# SheetAmpli.net
KiCad netlist of a schematic drawn in Altium Designer
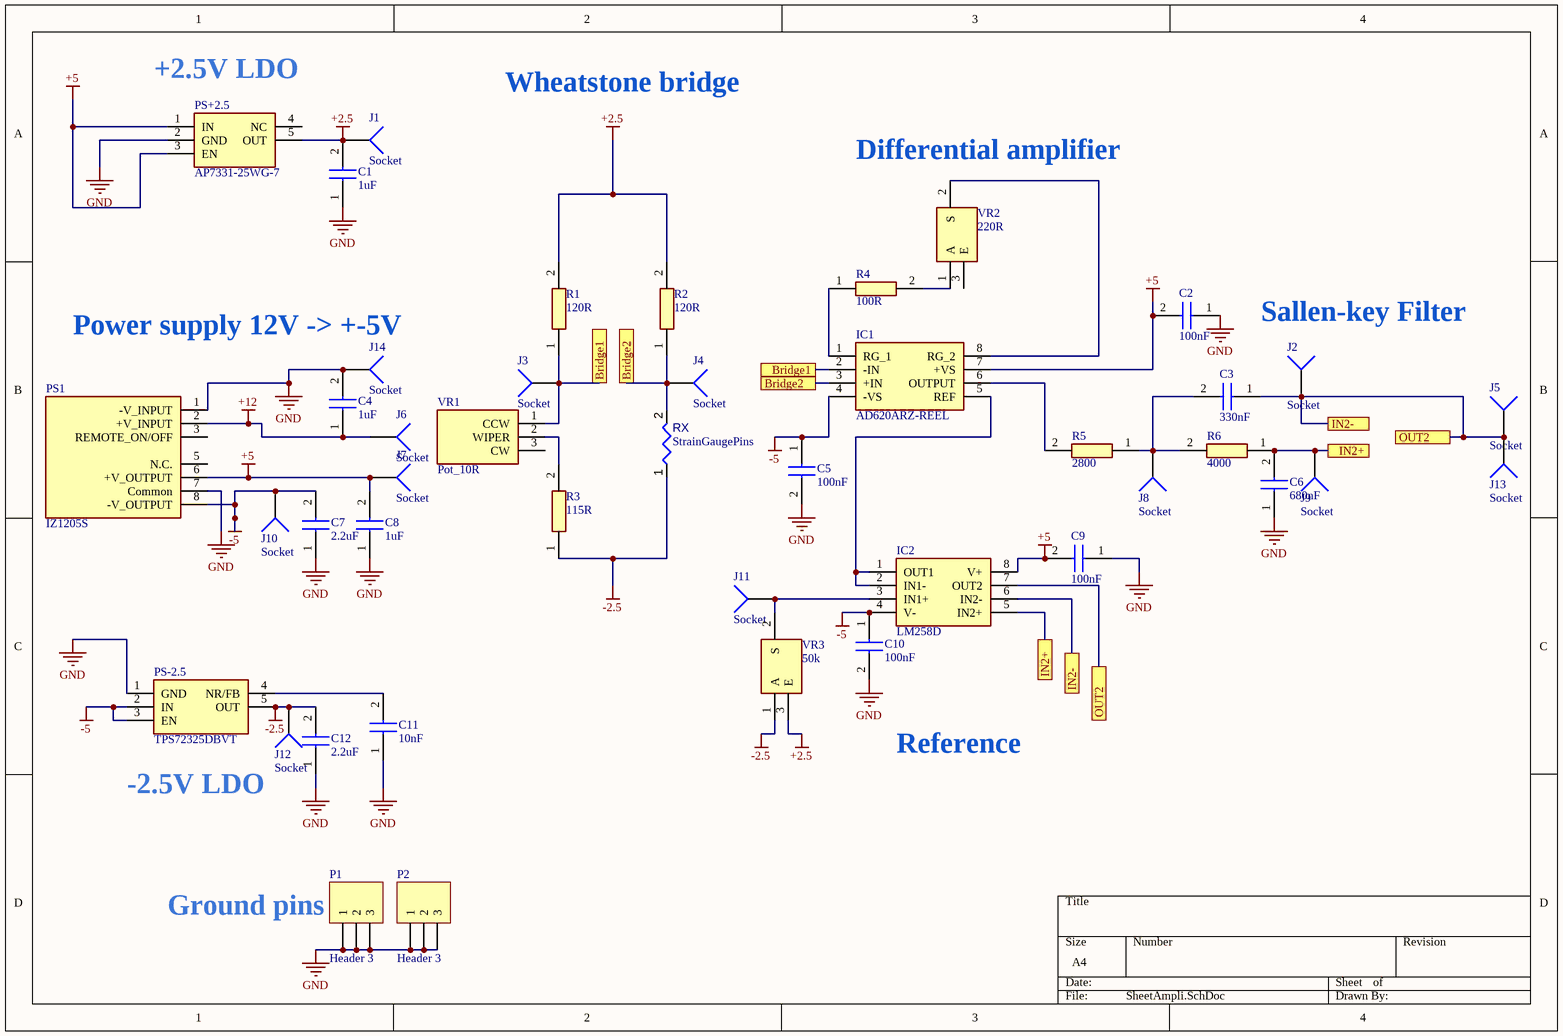
[diagram p0: SheetAmpli.SchDoc]

(export (version "E")
  (design (tool "Eeschema 10.0.6"))
  (components
    (comp (ref "C1")
      (value "1uF")
      (footprint "SamacSys:CAPC2012X94N")
      (description "Capacitor")
      (fields
        (field (name "MANUFACTURER_PART_NUMBER") "08055A130JAT2A")
        (field (name "MOUSER PART NUMBER") "581-08055A130JAT2A")
      )
      (libsource (lib "*") (part "08055A130JAT2A"))
    )
    (comp (ref "C2")
      (value "100nF")
      (footprint "SamacSys:CAPC2012X94N")
      (description "Capacitor")
      (fields
        (field (name "MANUFACTURER_PART_NUMBER") "08055A130JAT2A")
        (field (name "MOUSER PART NUMBER") "581-08055A130JAT2A")
      )
      (libsource (lib "*") (part "08055A130JAT2A"))
    )
    (comp (ref "C3")
      (value "330nF")
      (footprint "SamacSys:CAPC2012X94N")
      (description "Capacitor")
      (fields
        (field (name "MANUFACTURER_PART_NUMBER") "08055A130JAT2A")
        (field (name "MOUSER PART NUMBER") "581-08055A130JAT2A")
      )
      (libsource (lib "*") (part "08055A130JAT2A"))
    )
    (comp (ref "C4")
      (value "1uF")
      (footprint "SamacSys:CAPC2012X94N")
      (description "Capacitor")
      (fields
        (field (name "MANUFACTURER_PART_NUMBER") "08055A130JAT2A")
        (field (name "MOUSER PART NUMBER") "581-08055A130JAT2A")
      )
      (libsource (lib "*") (part "08055A130JAT2A"))
    )
    (comp (ref "C5")
      (value "100nF")
      (footprint "SamacSys:CAPC2012X94N")
      (description "Capacitor")
      (fields
        (field (name "MANUFACTURER_PART_NUMBER") "08055A130JAT2A")
        (field (name "MOUSER PART NUMBER") "581-08055A130JAT2A")
      )
      (libsource (lib "*") (part "08055A130JAT2A"))
    )
    (comp (ref "C6")
      (value "680nF")
      (footprint "SamacSys:CAPC2012X94N")
      (description "Capacitor")
      (fields
        (field (name "MANUFACTURER_PART_NUMBER") "08055A130JAT2A")
        (field (name "MOUSER PART NUMBER") "581-08055A130JAT2A")
      )
      (libsource (lib "*") (part "08055A130JAT2A"))
    )
    (comp (ref "C7")
      (value "2.2uF")
      (footprint "SamacSys:CAPC2012X94N")
      (description "Capacitor")
      (fields
        (field (name "MANUFACTURER_PART_NUMBER") "08055A130JAT2A")
        (field (name "MOUSER PART NUMBER") "581-08055A130JAT2A")
      )
      (libsource (lib "*") (part "08055A130JAT2A"))
    )
    (comp (ref "C8")
      (value "1uF")
      (footprint "SamacSys:CAPC2012X94N")
      (description "Capacitor")
      (fields
        (field (name "MANUFACTURER_PART_NUMBER") "08055A130JAT2A")
        (field (name "MOUSER PART NUMBER") "581-08055A130JAT2A")
      )
      (libsource (lib "*") (part "08055A130JAT2A"))
    )
    (comp (ref "C9")
      (value "100nF")
      (footprint "SamacSys:CAPC2012X94N")
      (description "Capacitor")
      (fields
        (field (name "MANUFACTURER_PART_NUMBER") "08055A130JAT2A")
        (field (name "MOUSER PART NUMBER") "581-08055A130JAT2A")
      )
      (libsource (lib "*") (part "08055A130JAT2A"))
    )
    (comp (ref "C10")
      (value "100nF")
      (footprint "SamacSys:CAPC2012X94N")
      (description "Capacitor")
      (fields
        (field (name "MANUFACTURER_PART_NUMBER") "08055A130JAT2A")
        (field (name "MOUSER PART NUMBER") "581-08055A130JAT2A")
      )
      (libsource (lib "*") (part "08055A130JAT2A"))
    )
    (comp (ref "C11")
      (value "10nF")
      (footprint "SamacSys:CAPC2012X94N")
      (description "Capacitor")
      (fields
        (field (name "MANUFACTURER_PART_NUMBER") "08055A130JAT2A")
        (field (name "MOUSER PART NUMBER") "581-08055A130JAT2A")
      )
      (libsource (lib "*") (part "08055A130JAT2A"))
    )
    (comp (ref "C12")
      (value "2.2uF")
      (footprint "SamacSys:CAPC2012X94N")
      (description "Capacitor")
      (fields
        (field (name "MANUFACTURER_PART_NUMBER") "08055A130JAT2A")
        (field (name "MOUSER PART NUMBER") "581-08055A130JAT2A")
      )
      (libsource (lib "*") (part "08055A130JAT2A"))
    )
    (comp (ref "IC1")
      (value "AD620ARZ-REEL")
      (footprint "SamacSys:SOIC127P600X175-8N")
      (description "Integrated Circuit")
      (fields (field (name "MOUSER PART NUMBER") "584-AD620ARZ-R"))
      (libsource (lib "*") (part "AD620ARZ-REEL"))
    )
    (comp (ref "IC2")
      (value "LM258D")
      (footprint "SamacSys:SOIC127P600X175-8N")
      (description "Integrated Circuit")
      (fields (field (name "MOUSER PART NUMBER") "595-LM258D"))
      (libsource (lib "*") (part "LM258D"))
    )
    (comp (ref "J1")
      (value "Socket")
      (footprint "PIN1")
      (fields (field (name "PUBLISHER") "Altium Limited"))
      (libsource (lib "Miscellaneous Connectors") (part "Socket"))
    )
    (comp (ref "J2")
      (value "Socket")
      (footprint "PIN1")
      (fields (field (name "PUBLISHER") "Altium Limited"))
      (libsource (lib "Miscellaneous Connectors") (part "Socket"))
    )
    (comp (ref "J3")
      (value "Socket")
      (footprint "PIN1")
      (fields (field (name "PUBLISHER") "Altium Limited"))
      (libsource (lib "Miscellaneous Connectors") (part "Socket"))
    )
    (comp (ref "J4")
      (value "Socket")
      (footprint "PIN1")
      (fields (field (name "PUBLISHER") "Altium Limited"))
      (libsource (lib "Miscellaneous Connectors") (part "Socket"))
    )
    (comp (ref "J5")
      (value "Socket")
      (footprint "PIN1")
      (fields (field (name "PUBLISHER") "Altium Limited"))
      (libsource (lib "Miscellaneous Connectors") (part "Socket"))
    )
    (comp (ref "J6")
      (value "Socket")
      (footprint "PIN1")
      (fields (field (name "PUBLISHER") "Altium Limited"))
      (libsource (lib "Miscellaneous Connectors") (part "Socket"))
    )
    (comp (ref "J7")
      (value "Socket")
      (footprint "PIN1")
      (fields (field (name "PUBLISHER") "Altium Limited"))
      (libsource (lib "Miscellaneous Connectors") (part "Socket"))
    )
    (comp (ref "J8")
      (value "Socket")
      (footprint "PIN1")
      (fields (field (name "PUBLISHER") "Altium Limited"))
      (libsource (lib "Miscellaneous Connectors") (part "Socket"))
    )
    (comp (ref "J9")
      (value "Socket")
      (footprint "PIN1")
      (fields (field (name "PUBLISHER") "Altium Limited"))
      (libsource (lib "Miscellaneous Connectors") (part "Socket"))
    )
    (comp (ref "J10")
      (value "Socket")
      (footprint "PIN1")
      (fields (field (name "PUBLISHER") "Altium Limited"))
      (libsource (lib "Miscellaneous Connectors") (part "Socket"))
    )
    (comp (ref "J11")
      (value "Socket")
      (footprint "PIN1")
      (fields (field (name "PUBLISHER") "Altium Limited"))
      (libsource (lib "Miscellaneous Connectors") (part "Socket"))
    )
    (comp (ref "J12")
      (value "Socket")
      (footprint "PIN1")
      (fields (field (name "PUBLISHER") "Altium Limited"))
      (libsource (lib "Miscellaneous Connectors") (part "Socket"))
    )
    (comp (ref "J13")
      (value "Socket")
      (footprint "PIN1")
      (fields (field (name "PUBLISHER") "Altium Limited"))
      (libsource (lib "Miscellaneous Connectors") (part "Socket"))
    )
    (comp (ref "J14")
      (value "Socket")
      (footprint "PIN1")
      (fields (field (name "PUBLISHER") "Altium Limited"))
      (libsource (lib "Miscellaneous Connectors") (part "Socket"))
    )
    (comp (ref "P1")
      (value "Header 3")
      (footprint "HDR1X3")
      (description "Header, 3-Pin")
      (fields (field (name "PUBLISHER") "Altium Limited"))
      (libsource (lib "Miscellaneous Connectors") (part "Header 3"))
    )
    (comp (ref "P2")
      (value "Header 3")
      (footprint "HDR1X3")
      (description "Header, 3-Pin")
      (fields (field (name "PUBLISHER") "Altium Limited"))
      (libsource (lib "Miscellaneous Connectors") (part "Header 3"))
    )
    (comp (ref "PS+2.5")
      (value "AP7331-25WG-7")
      (footprint "SamacSys:SOT95P285X130-5N")
      (description "Power Supply")
      (fields
        (field (name "MANUFACTURER_PART_NUMBER") "AP7331-33WG-7")
        (field (name "MOUSER PART NUMBER") "621-AP7331-33WG-7")
      )
      (libsource (lib "SamacSys") (part "AP7331-33WG-7"))
    )
    (comp (ref "PS-2.5")
      (value "TPS72325DBVT")
      (footprint "SamacSys:SOT95P280X145-5N")
      (description "Integrated Circuit")
      (fields (field (name "MOUSER PART NUMBER") "595-TPS72325DBVT"))
      (libsource (lib "*") (part "TPS72325DBVT"))
    )
    (comp (ref "PS1")
      (value "IZ1205S")
      (footprint "SamacSys:IZ1205S")
      (description "Power Supply")
      (fields (field (name "MOUSER PART NUMBER") "209-IZ1205S"))
      (libsource (lib "*") (part "IZ1205S"))
    )
    (comp (ref "R1")
      (value "120R")
      (footprint "SamacSys:RESC2012X65N")
      (description "Resistor")
      (fields
        (field (name "MANUFACTURER_PART_NUMBER") "CRG0805F100K")
        (field (name "MOUSER PART NUMBER") "279-CRG0805F100K")
      )
      (libsource (lib "") (part "CRG0805F100K_1"))
    )
    (comp (ref "R2")
      (value "120R")
      (footprint "SamacSys:RESC2012X65N")
      (description "Resistor")
      (fields
        (field (name "MANUFACTURER_PART_NUMBER") "CRG0805F100K")
        (field (name "MOUSER PART NUMBER") "279-CRG0805F100K")
      )
      (libsource (lib "") (part "CRG0805F100K_1"))
    )
    (comp (ref "R3")
      (value "115R")
      (footprint "SamacSys:RESC2012X65N")
      (description "Resistor")
      (fields
        (field (name "MANUFACTURER_PART_NUMBER") "CRG0805F100K")
        (field (name "MOUSER PART NUMBER") "279-CRG0805F100K")
      )
      (libsource (lib "") (part "CRG0805F100K_1"))
    )
    (comp (ref "R4")
      (value "100R")
      (footprint "SamacSys:RESC2012X65N")
      (description "Resistor")
      (fields
        (field (name "MANUFACTURER_PART_NUMBER") "CRG0805F100K")
        (field (name "MOUSER PART NUMBER") "279-CRG0805F100K")
      )
      (libsource (lib "") (part "CRG0805F100K_2"))
    )
    (comp (ref "R5")
      (value "2800")
      (footprint "SamacSys:RESC2012X65N")
      (description "Resistor")
      (fields
        (field (name "MANUFACTURER_PART_NUMBER") "CRG0805F100K")
        (field (name "MOUSER PART NUMBER") "279-CRG0805F100K")
      )
      (libsource (lib "SamacSys") (part "CRG0805F100K"))
    )
    (comp (ref "R6")
      (value "4000")
      (footprint "SamacSys:RESC2012X65N")
      (description "Resistor")
      (fields
        (field (name "MANUFACTURER_PART_NUMBER") "CRG0805F100K")
        (field (name "MOUSER PART NUMBER") "279-CRG0805F100K")
      )
      (libsource (lib "SamacSys") (part "CRG0805F100K"))
    )
    (comp (ref "RX")
      (value "StrainGaugePins")
      (footprint "RESA60-630X240")
      (description "Axial Resistor, 100 KOhm, +/- 1%, 0.25 W, -55 to 155 degC, 2-Pin THD, RoHS, Bulk")
      (fields (field (name "MANUFACTURER") "Yageo") (field (name "POWER") "250mW"))
      (libsource (lib "Universite Libre De Bruxelles") (part "RES-2"))
    )
    (comp (ref "VR1")
      (value "Pot_10R")
      (footprint "SamacSys:3296W-1")
      (description "Variable Resistor")
      (fields
        (field (name "MANUFACTURER_PART_NUMBER") "3296W-1-103LF")
        (field (name "MOUSER PART NUMBER") "652-3296W-1-103LF")
      )
      (libsource (lib "*") (part "3296W-1-103LF"))
    )
    (comp (ref "VR2")
      (value "220R")
      (footprint "SamacSys:PT10LV10473A2020PMS")
      (description "Variable Resistor")
      (fields
        (field (name "MANUFACTURER_PART_NUMBER") "PT10LV10-103A2020")
        (field (name "MOUSER PART NUMBER") "531-PT10V-10K")
      )
      (libsource (lib "SamacSys") (part "PT10LV10-103A2020"))
    )
    (comp (ref "VR3")
      (value "50k")
      (footprint "SamacSys:PT10LV10473A2020PMS")
      (description "Variable Resistor")
      (fields
        (field (name "MANUFACTURER_PART_NUMBER") "PT10LV10-103A2020")
        (field (name "MOUSER PART NUMBER") "531-PT10V-10K")
      )
      (libsource (lib "SamacSys") (part "PT10LV10-103A2020"))
    )
  )
  (nets
    (net (code "1") (name "+2.5") (class "Default")
      (node (ref "C1") (pin "2") (pinfunction "2_2") (pintype "passive"))
      (node (ref "J1") (pin "1") (pinfunction "1_1") (pintype "passive"))
      (node (ref "PS+2.5") (pin "5") (pinfunction "OUT_5") (pintype "passive"))
      (node (ref "R1") (pin "2") (pinfunction "2_2") (pintype "passive"))
      (node (ref "R2") (pin "2") (pinfunction "2_2") (pintype "passive"))
      (node (ref "VR3") (pin "3") (pinfunction "E_3") (pintype "passive"))
    )
    (net (code "2") (name "+5") (class "Default")
      (node (ref "C2") (pin "2") (pinfunction "2_2") (pintype "passive"))
      (node (ref "C8") (pin "2") (pinfunction "2_2") (pintype "passive"))
      (node (ref "C9") (pin "2") (pinfunction "2_2") (pintype "passive"))
      (node (ref "IC1") (pin "7") (pinfunction "+VS_7") (pintype "passive"))
      (node (ref "IC2") (pin "8") (pinfunction "V+_8") (pintype "passive"))
      (node (ref "J7") (pin "1") (pinfunction "1_1") (pintype "passive"))
      (node (ref "PS+2.5") (pin "1") (pinfunction "IN_1") (pintype "passive"))
      (node (ref "PS+2.5") (pin "3") (pinfunction "EN_3") (pintype "passive"))
      (node (ref "PS1") (pin "6") (pinfunction "+V_OUTPUT_6") (pintype "passive"))
    )
    (net (code "3") (name "+12") (class "Default")
      (node (ref "C4") (pin "1") (pinfunction "1_1") (pintype "passive"))
      (node (ref "J6") (pin "1") (pinfunction "1_1") (pintype "passive"))
      (node (ref "PS1") (pin "2") (pinfunction "+V_INPUT_2") (pintype "passive"))
    )
    (net (code "4") (name "-2.5") (class "Default")
      (node (ref "C12") (pin "2") (pinfunction "2_2") (pintype "passive"))
      (node (ref "J12") (pin "1") (pinfunction "1_1") (pintype "passive"))
      (node (ref "PS-2.5") (pin "5") (pinfunction "OUT_5") (pintype "passive"))
      (node (ref "R3") (pin "1") (pinfunction "1_1") (pintype "passive"))
      (node (ref "RX") (pin "1") (pinfunction "1_1") (pintype "passive"))
      (node (ref "VR3") (pin "1") (pinfunction "A_1") (pintype "passive"))
    )
    (net (code "5") (name "-5") (class "Default")
      (node (ref "C10") (pin "1") (pinfunction "1_1") (pintype "passive"))
      (node (ref "C5") (pin "1") (pinfunction "1_1") (pintype "passive"))
      (node (ref "C7") (pin "2") (pinfunction "2_2") (pintype "passive"))
      (node (ref "IC1") (pin "4") (pinfunction "-VS_4") (pintype "passive"))
      (node (ref "IC2") (pin "4") (pinfunction "V-_4") (pintype "passive"))
      (node (ref "J10") (pin "1") (pinfunction "1_1") (pintype "passive"))
      (node (ref "PS-2.5") (pin "2") (pinfunction "IN_2") (pintype "passive"))
      (node (ref "PS-2.5") (pin "3") (pinfunction "EN_3") (pintype "passive"))
      (node (ref "PS1") (pin "8") (pinfunction "-V_OUTPUT_8") (pintype "passive"))
    )
    (net (code "6") (name "/Bridge1") (class "Default")
      (node (ref "IC1") (pin "2") (pinfunction "-IN_2") (pintype "passive"))
      (node (ref "J3") (pin "1") (pinfunction "1_1") (pintype "passive"))
      (node (ref "R1") (pin "1") (pinfunction "1_1") (pintype "passive"))
      (node (ref "VR1") (pin "1") (pinfunction "CCW_1") (pintype "passive"))
    )
    (net (code "7") (name "/Bridge2") (class "Default")
      (node (ref "IC1") (pin "3") (pinfunction "+IN_3") (pintype "passive"))
      (node (ref "J4") (pin "1") (pinfunction "1_1") (pintype "passive"))
      (node (ref "R2") (pin "1") (pinfunction "1_1") (pintype "passive"))
      (node (ref "RX") (pin "2") (pinfunction "2_2") (pintype "passive"))
    )
    (net (code "8") (name "/IN2+") (class "Default")
      (node (ref "C6") (pin "2") (pinfunction "2_2") (pintype "passive"))
      (node (ref "IC2") (pin "5") (pinfunction "IN2+_5") (pintype "passive"))
      (node (ref "J9") (pin "1") (pinfunction "1_1") (pintype "passive"))
      (node (ref "R6") (pin "1") (pinfunction "1_1") (pintype "passive"))
    )
    (net (code "9") (name "/IN2-") (class "Default")
      (node (ref "C3") (pin "1") (pinfunction "1_1") (pintype "passive"))
      (node (ref "IC2") (pin "6") (pinfunction "IN2-_6") (pintype "passive"))
      (node (ref "IC2") (pin "7") (pinfunction "OUT2_7") (pintype "passive"))
      (node (ref "J13") (pin "1") (pinfunction "1_1") (pintype "passive"))
      (node (ref "J2") (pin "1") (pinfunction "1_1") (pintype "passive"))
      (node (ref "J5") (pin "1") (pinfunction "1_1") (pintype "passive"))
    )
    (net (code "10") (name "GND") (class "Default")
      (node (ref "C1") (pin "1") (pinfunction "1_1") (pintype "passive"))
      (node (ref "C10") (pin "2") (pinfunction "2_2") (pintype "passive"))
      (node (ref "C11") (pin "1") (pinfunction "1_1") (pintype "passive"))
      (node (ref "C12") (pin "1") (pinfunction "1_1") (pintype "passive"))
      (node (ref "C2") (pin "1") (pinfunction "1_1") (pintype "passive"))
      (node (ref "C4") (pin "2") (pinfunction "2_2") (pintype "passive"))
      (node (ref "C5") (pin "2") (pinfunction "2_2") (pintype "passive"))
      (node (ref "C6") (pin "1") (pinfunction "1_1") (pintype "passive"))
      (node (ref "C7") (pin "1") (pinfunction "1_1") (pintype "passive"))
      (node (ref "C8") (pin "1") (pinfunction "1_1") (pintype "passive"))
      (node (ref "C9") (pin "1") (pinfunction "1_1") (pintype "passive"))
      (node (ref "J14") (pin "1") (pinfunction "1_1") (pintype "passive"))
      (node (ref "P1") (pin "1") (pinfunction "1_1") (pintype "passive"))
      (node (ref "P1") (pin "2") (pinfunction "2_2") (pintype "passive"))
      (node (ref "P1") (pin "3") (pinfunction "3_3") (pintype "passive"))
      (node (ref "P2") (pin "1") (pinfunction "1_1") (pintype "passive"))
      (node (ref "P2") (pin "2") (pinfunction "2_2") (pintype "passive"))
      (node (ref "P2") (pin "3") (pinfunction "3_3") (pintype "passive"))
      (node (ref "PS+2.5") (pin "2") (pinfunction "GND_2") (pintype "passive"))
      (node (ref "PS-2.5") (pin "1") (pinfunction "GND_1") (pintype "passive"))
      (node (ref "PS1") (pin "1") (pinfunction "-V_INPUT_1") (pintype "passive"))
      (node (ref "PS1") (pin "7") (pinfunction "Common_7") (pintype "passive"))
    )
    (net (code "11") (name "Net-(C3-Pad2)") (class "Default")
      (node (ref "C3") (pin "2") (pinfunction "2_2") (pintype "passive"))
      (node (ref "J8") (pin "1") (pinfunction "1_1") (pintype "passive"))
      (node (ref "R5") (pin "1") (pinfunction "1_1") (pintype "passive"))
      (node (ref "R6") (pin "2") (pinfunction "2_2") (pintype "passive"))
    )
    (net (code "12") (name "Net-(IC1-OUTPUT)") (class "Default")
      (node (ref "IC1") (pin "6") (pinfunction "OUTPUT_6") (pintype "passive"))
      (node (ref "R5") (pin "2") (pinfunction "2_2") (pintype "passive"))
    )
    (net (code "13") (name "Net-(IC1-REF)") (class "Default")
      (node (ref "IC1") (pin "5") (pinfunction "REF_5") (pintype "passive"))
      (node (ref "IC2") (pin "1") (pinfunction "OUT1_1") (pintype "passive"))
      (node (ref "IC2") (pin "2") (pinfunction "IN1-_2") (pintype "passive"))
    )
    (net (code "14") (name "Net-(IC1-RG_1)") (class "Default")
      (node (ref "IC1") (pin "1") (pinfunction "RG_1_1") (pintype "passive"))
      (node (ref "R4") (pin "1") (pinfunction "1_1") (pintype "passive"))
    )
    (net (code "15") (name "Net-(IC1-RG_2)") (class "Default")
      (node (ref "IC1") (pin "8") (pinfunction "RG_2_8") (pintype "passive"))
      (node (ref "VR2") (pin "2") (pinfunction "S_2") (pintype "passive"))
    )
    (net (code "16") (name "Net-(IC2-IN1+)") (class "Default")
      (node (ref "IC2") (pin "3") (pinfunction "IN1+_3") (pintype "passive"))
      (node (ref "J11") (pin "1") (pinfunction "1_1") (pintype "passive"))
      (node (ref "VR3") (pin "2") (pinfunction "S_2") (pintype "passive"))
    )
    (net (code "17") (name "Net-(PS-2.5-NR{slash}FB)") (class "Default")
      (node (ref "C11") (pin "2") (pinfunction "2_2") (pintype "passive"))
      (node (ref "PS-2.5") (pin "4") (pinfunction "NR/FB_4") (pintype "passive"))
    )
    (net (code "18") (name "Net-(VR1-WIPER)") (class "Default")
      (node (ref "R3") (pin "2") (pinfunction "2_2") (pintype "passive"))
      (node (ref "VR1") (pin "2") (pinfunction "WIPER_2") (pintype "passive"))
    )
    (net (code "19") (name "Net-(VR2-A)") (class "Default")
      (node (ref "R4") (pin "2") (pinfunction "2_2") (pintype "passive"))
      (node (ref "VR2") (pin "1") (pinfunction "A_1") (pintype "passive"))
    )
    (net (code "20") (name "unconnected-(PS+2.5-NC-Pad4)") (class "Default")
      (node (ref "PS+2.5") (pin "4") (pinfunction "NC_4") (pintype "passive"))
    )
    (net (code "21") (name "unconnected-(PS1-N.C.-Pad5)") (class "Default")
      (node (ref "PS1") (pin "5") (pinfunction "N.C._5") (pintype "passive"))
    )
    (net (code "22") (name "unconnected-(PS1-REMOTE_ON{slash}OFF-Pad3)") (class "Default")
      (node (ref "PS1") (pin "3") (pinfunction "REMOTE_ON/OFF_3") (pintype "passive"))
    )
    (net (code "23") (name "unconnected-(VR1-CW-Pad3)") (class "Default")
      (node (ref "VR1") (pin "3") (pinfunction "CW_3") (pintype "passive"))
    )
    (net (code "24") (name "unconnected-(VR2-E-Pad3)") (class "Default")
      (node (ref "VR2") (pin "3") (pinfunction "E_3") (pintype "passive"))
    )
  )
)
